# Sequencer_RevD.net
KiCad netlist of a schematic drawn in EAGLE
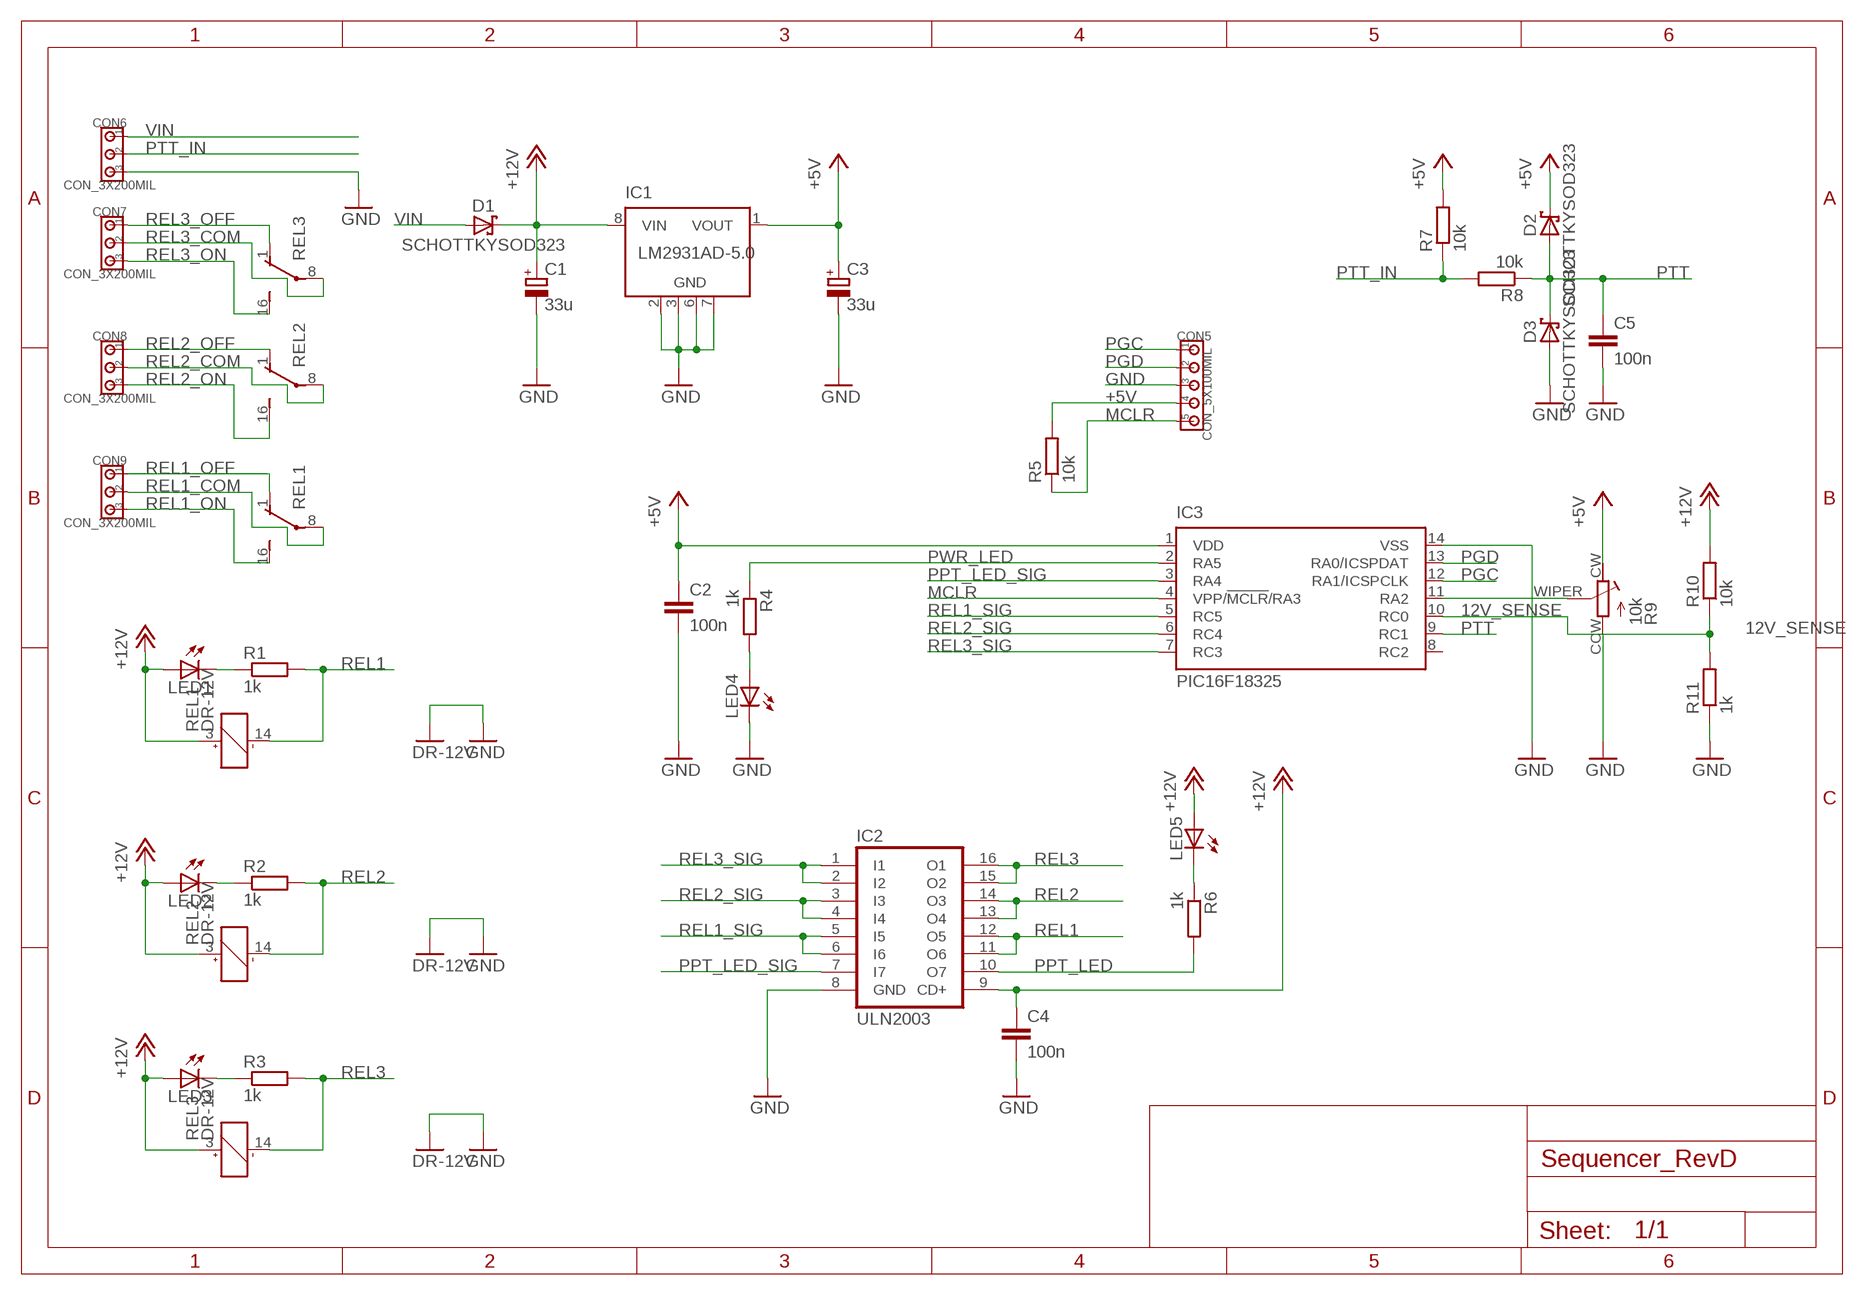
[diagram p0: schematic, sheet 1]

(export (version "E")
  (design (tool "Eeschema 10.0.6"))
  (components
    (comp (ref "C1")
      (value "33u")
      (footprint "eagle-import:SMC_C")
      (libsource (lib "eagle-import") (part "C_POLARIZEDSMC_C"))
    )
    (comp (ref "C2")
      (value "100n")
      (footprint "eagle-import:C0805")
      (libsource (lib "eagle-import") (part "CC0805"))
    )
    (comp (ref "C3")
      (value "33u")
      (footprint "eagle-import:SMC_C")
      (libsource (lib "eagle-import") (part "C_POLARIZEDSMC_C"))
    )
    (comp (ref "C4")
      (value "100n")
      (footprint "eagle-import:C0805")
      (libsource (lib "eagle-import") (part "CC0805"))
    )
    (comp (ref "C5")
      (value "100n")
      (footprint "eagle-import:C0805")
      (libsource (lib "eagle-import") (part "CC0805"))
    )
    (comp (ref "CON5")
      (value "CON_5X100MIL")
      (footprint "eagle-import:100MIL_5X")
      (libsource (lib "eagle-import") (part "CON_5X100MIL"))
    )
    (comp (ref "CON6")
      (value "CON_3X200MIL")
      (footprint "eagle-import:200MIL_3X")
      (libsource (lib "eagle-import") (part "CON_3X200MIL"))
    )
    (comp (ref "CON7")
      (value "CON_3X200MIL")
      (footprint "eagle-import:200MIL_3X")
      (libsource (lib "eagle-import") (part "CON_3X200MIL"))
    )
    (comp (ref "CON8")
      (value "CON_3X200MIL")
      (footprint "eagle-import:200MIL_3X")
      (libsource (lib "eagle-import") (part "CON_3X200MIL"))
    )
    (comp (ref "CON9")
      (value "CON_3X200MIL")
      (footprint "eagle-import:200MIL_3X")
      (libsource (lib "eagle-import") (part "CON_3X200MIL"))
    )
    (comp (ref "D1")
      (value "SCHOTTKYSOD323")
      (footprint "eagle-import:SOD323")
      (libsource (lib "eagle-import") (part "SCHOTTKYSOD323"))
    )
    (comp (ref "D2")
      (value "SCHOTTKYSOD323")
      (footprint "eagle-import:SOD323")
      (libsource (lib "eagle-import") (part "SCHOTTKYSOD323"))
    )
    (comp (ref "D3")
      (value "SCHOTTKYSOD323")
      (footprint "eagle-import:SOD323")
      (libsource (lib "eagle-import") (part "SCHOTTKYSOD323"))
    )
    (comp (ref "IC1")
      (value "LM2931AD-5.0")
      (footprint "eagle-import:SOIC8")
      (libsource (lib "eagle-import") (part "LM2931AD-5.0"))
    )
    (comp (ref "IC2")
      (value "ULN2003")
      (footprint "eagle-import:SO16")
      (libsource (lib "eagle-import") (part "ULN2003"))
    )
    (comp (ref "IC3")
      (value "PIC16F18325")
      (footprint "eagle-import:SO14")
      (libsource (lib "eagle-import") (part "PIC16F18325"))
    )
    (comp (ref "LED1")
      (value "LED0805")
      (footprint "eagle-import:LED0805")
      (libsource (lib "eagle-import") (part "LED0805"))
    )
    (comp (ref "LED2")
      (value "LED0805")
      (footprint "eagle-import:LED0805")
      (libsource (lib "eagle-import") (part "LED0805"))
    )
    (comp (ref "LED3")
      (value "LED0805")
      (footprint "eagle-import:LED0805")
      (libsource (lib "eagle-import") (part "LED0805"))
    )
    (comp (ref "LED4")
      (value "LED0805")
      (footprint "eagle-import:LED0805")
      (libsource (lib "eagle-import") (part "LED0805"))
    )
    (comp (ref "LED5")
      (value "LED0805")
      (footprint "eagle-import:LED0805")
      (libsource (lib "eagle-import") (part "LED0805"))
    )
    (comp (ref "R1")
      (value "1k")
      (footprint "eagle-import:R0805")
      (libsource (lib "eagle-import") (part "RESISTORR0805"))
    )
    (comp (ref "R2")
      (value "1k")
      (footprint "eagle-import:R0805")
      (libsource (lib "eagle-import") (part "RESISTORR0805"))
    )
    (comp (ref "R3")
      (value "1k")
      (footprint "eagle-import:R0805")
      (libsource (lib "eagle-import") (part "RESISTORR0805"))
    )
    (comp (ref "R4")
      (value "1k")
      (footprint "eagle-import:R0805")
      (libsource (lib "eagle-import") (part "RESISTORR0805"))
    )
    (comp (ref "R5")
      (value "10k")
      (footprint "eagle-import:R0805")
      (libsource (lib "eagle-import") (part "RESISTORR0805"))
    )
    (comp (ref "R6")
      (value "1k")
      (footprint "eagle-import:R0805")
      (libsource (lib "eagle-import") (part "RESISTORR0805"))
    )
    (comp (ref "R7")
      (value "10k")
      (footprint "eagle-import:R0805")
      (libsource (lib "eagle-import") (part "RESISTORR0805"))
    )
    (comp (ref "R8")
      (value "10k")
      (footprint "eagle-import:R0805")
      (libsource (lib "eagle-import") (part "RESISTORR0805"))
    )
    (comp (ref "R9")
      (value "10k")
      (footprint "eagle-import:RTRIM3314G")
      (libsource (lib "eagle-import") (part "TRIMMER3314G"))
    )
    (comp (ref "R10")
      (value "10k")
      (footprint "eagle-import:R0805")
      (libsource (lib "eagle-import") (part "RESISTORR0805"))
    )
    (comp (ref "R11")
      (value "1k")
      (footprint "eagle-import:R0805")
      (libsource (lib "eagle-import") (part "RESISTORR0805"))
    )
    (comp (ref "REL1")
      (value "DR-12V")
      (footprint "eagle-import:DR-12V")
      (libsource (lib "eagle-import") (part "DR-12V"))
    )
    (comp (ref "REL2")
      (value "DR-12V")
      (footprint "eagle-import:DR-12V")
      (libsource (lib "eagle-import") (part "DR-12V"))
    )
    (comp (ref "REL3")
      (value "DR-12V")
      (footprint "eagle-import:DR-12V")
      (libsource (lib "eagle-import") (part "DR-12V"))
    )
  )
  (nets
    (net (code "1") (name "+5V") (class "Default")
      (node (ref "C2") (pin "1") (pinfunction "1_1") (pintype "passive"))
      (node (ref "C3") (pin "+") (pinfunction "+_+") (pintype "passive"))
      (node (ref "CON5") (pin "4") (pinfunction "4_4") (pintype "passive"))
      (node (ref "D2") (pin "C") (pinfunction "C_C") (pintype "passive"))
      (node (ref "IC1") (pin "1") (pinfunction "VOUT_1") (pintype "output"))
      (node (ref "IC3") (pin "1") (pinfunction "VDD_1") (pintype "power_in"))
      (node (ref "R5") (pin "2") (pinfunction "2_2") (pintype "passive"))
      (node (ref "R7") (pin "2") (pinfunction "2_2") (pintype "passive"))
      (node (ref "R9") (pin "CW") (pinfunction "CW_CW") (pintype "passive"))
    )
    (net (code "2") (name "+12V") (class "Default")
      (node (ref "C1") (pin "+") (pinfunction "+_+") (pintype "passive"))
      (node (ref "C4") (pin "1") (pinfunction "1_1") (pintype "passive"))
      (node (ref "D1") (pin "C") (pinfunction "C_C") (pintype "passive"))
      (node (ref "IC1") (pin "8") (pinfunction "VIN_8") (pintype "passive"))
      (node (ref "IC2") (pin "9") (pinfunction "CD+_9") (pintype "passive"))
      (node (ref "LED1") (pin "A") (pinfunction "A_A") (pintype "passive"))
      (node (ref "LED2") (pin "A") (pinfunction "A_A") (pintype "passive"))
      (node (ref "LED3") (pin "A") (pinfunction "A_A") (pintype "passive"))
      (node (ref "LED5") (pin "A") (pinfunction "A_A") (pintype "passive"))
      (node (ref "R10") (pin "2") (pinfunction "2_2") (pintype "passive"))
      (node (ref "REL1") (pin "3") (pinfunction "+_3") (pintype "passive"))
      (node (ref "REL2") (pin "3") (pinfunction "+_3") (pintype "passive"))
      (node (ref "REL3") (pin "3") (pinfunction "+_3") (pintype "passive"))
    )
    (net (code "3") (name "/12V_SENSE") (class "Default")
      (node (ref "IC3") (pin "10") (pinfunction "RC0_10") (pintype "bidirectional"))
      (node (ref "R10") (pin "1") (pinfunction "1_1") (pintype "passive"))
      (node (ref "R11") (pin "2") (pinfunction "2_2") (pintype "passive"))
    )
    (net (code "4") (name "/MCLR") (class "Default")
      (node (ref "CON5") (pin "5") (pinfunction "5_5") (pintype "passive"))
      (node (ref "IC3") (pin "4") (pinfunction "VPP/~{MCLR}/RA3_4") (pintype "bidirectional"))
      (node (ref "R5") (pin "1") (pinfunction "1_1") (pintype "passive"))
    )
    (net (code "5") (name "/PGC") (class "Default")
      (node (ref "CON5") (pin "1") (pinfunction "1_1") (pintype "passive"))
      (node (ref "IC3") (pin "12") (pinfunction "RA1/ICSPCLK_12") (pintype "bidirectional"))
    )
    (net (code "6") (name "/PGD") (class "Default")
      (node (ref "CON5") (pin "2") (pinfunction "2_2") (pintype "passive"))
      (node (ref "IC3") (pin "13") (pinfunction "RA0/ICSPDAT_13") (pintype "bidirectional"))
    )
    (net (code "7") (name "/PPT_LED") (class "Default")
      (node (ref "IC2") (pin "10") (pinfunction "O7_10") (pintype "open_collector"))
      (node (ref "R6") (pin "2") (pinfunction "2_2") (pintype "passive"))
    )
    (net (code "8") (name "/PPT_LED_SIG") (class "Default")
      (node (ref "IC2") (pin "7") (pinfunction "I7_7") (pintype "input"))
      (node (ref "IC3") (pin "3") (pinfunction "RA4_3") (pintype "bidirectional"))
    )
    (net (code "9") (name "/PTT") (class "Default")
      (node (ref "C5") (pin "1") (pinfunction "1_1") (pintype "passive"))
      (node (ref "D2") (pin "A") (pinfunction "A_A") (pintype "passive"))
      (node (ref "D3") (pin "C") (pinfunction "C_C") (pintype "passive"))
      (node (ref "IC3") (pin "9") (pinfunction "RC1_9") (pintype "bidirectional"))
      (node (ref "R8") (pin "1") (pinfunction "1_1") (pintype "passive"))
    )
    (net (code "10") (name "/PTT_IN") (class "Default")
      (node (ref "CON6") (pin "2") (pinfunction "2_2") (pintype "passive"))
      (node (ref "R7") (pin "1") (pinfunction "1_1") (pintype "passive"))
      (node (ref "R8") (pin "2") (pinfunction "2_2") (pintype "passive"))
    )
    (net (code "11") (name "/PWR_LED") (class "Default")
      (node (ref "IC3") (pin "2") (pinfunction "RA5_2") (pintype "input"))
      (node (ref "R4") (pin "1") (pinfunction "1_1") (pintype "passive"))
    )
    (net (code "12") (name "/REL1") (class "Default")
      (node (ref "IC2") (pin "11") (pinfunction "O6_11") (pintype "open_collector"))
      (node (ref "IC2") (pin "12") (pinfunction "O5_12") (pintype "open_collector"))
      (node (ref "R1") (pin "2") (pinfunction "2_2") (pintype "passive"))
      (node (ref "REL1") (pin "14") (pinfunction "-_14") (pintype "passive"))
    )
    (net (code "13") (name "/REL1_COM") (class "Default")
      (node (ref "CON9") (pin "2") (pinfunction "2_2") (pintype "passive"))
      (node (ref "REL1") (pin "8") (pinfunction "P_8") (pintype "passive"))
    )
    (net (code "14") (name "/REL1_OFF") (class "Default")
      (node (ref "CON9") (pin "1") (pinfunction "1_1") (pintype "passive"))
      (node (ref "REL1") (pin "1") (pinfunction "O_1") (pintype "passive"))
    )
    (net (code "15") (name "/REL1_ON") (class "Default")
      (node (ref "CON9") (pin "3") (pinfunction "3_3") (pintype "passive"))
      (node (ref "REL1") (pin "16") (pinfunction "S_16") (pintype "passive"))
    )
    (net (code "16") (name "/REL1_SIG") (class "Default")
      (node (ref "IC2") (pin "5") (pinfunction "I5_5") (pintype "input"))
      (node (ref "IC2") (pin "6") (pinfunction "I6_6") (pintype "input"))
      (node (ref "IC3") (pin "5") (pinfunction "RC5_5") (pintype "bidirectional"))
    )
    (net (code "17") (name "/REL2") (class "Default")
      (node (ref "IC2") (pin "13") (pinfunction "O4_13") (pintype "open_collector"))
      (node (ref "IC2") (pin "14") (pinfunction "O3_14") (pintype "open_collector"))
      (node (ref "R2") (pin "2") (pinfunction "2_2") (pintype "passive"))
      (node (ref "REL2") (pin "14") (pinfunction "-_14") (pintype "passive"))
    )
    (net (code "18") (name "/REL2_COM") (class "Default")
      (node (ref "CON8") (pin "2") (pinfunction "2_2") (pintype "passive"))
      (node (ref "REL2") (pin "8") (pinfunction "P_8") (pintype "passive"))
    )
    (net (code "19") (name "/REL2_OFF") (class "Default")
      (node (ref "CON8") (pin "1") (pinfunction "1_1") (pintype "passive"))
      (node (ref "REL2") (pin "1") (pinfunction "O_1") (pintype "passive"))
    )
    (net (code "20") (name "/REL2_ON") (class "Default")
      (node (ref "CON8") (pin "3") (pinfunction "3_3") (pintype "passive"))
      (node (ref "REL2") (pin "16") (pinfunction "S_16") (pintype "passive"))
    )
    (net (code "21") (name "/REL2_SIG") (class "Default")
      (node (ref "IC2") (pin "3") (pinfunction "I3_3") (pintype "input"))
      (node (ref "IC2") (pin "4") (pinfunction "I4_4") (pintype "input"))
      (node (ref "IC3") (pin "6") (pinfunction "RC4_6") (pintype "bidirectional"))
    )
    (net (code "22") (name "/REL3") (class "Default")
      (node (ref "IC2") (pin "15") (pinfunction "O2_15") (pintype "open_collector"))
      (node (ref "IC2") (pin "16") (pinfunction "O1_16") (pintype "open_collector"))
      (node (ref "R3") (pin "2") (pinfunction "2_2") (pintype "passive"))
      (node (ref "REL3") (pin "14") (pinfunction "-_14") (pintype "passive"))
    )
    (net (code "23") (name "/REL3_COM") (class "Default")
      (node (ref "CON7") (pin "2") (pinfunction "2_2") (pintype "passive"))
      (node (ref "REL3") (pin "8") (pinfunction "P_8") (pintype "passive"))
    )
    (net (code "24") (name "/REL3_OFF") (class "Default")
      (node (ref "CON7") (pin "1") (pinfunction "1_1") (pintype "passive"))
      (node (ref "REL3") (pin "1") (pinfunction "O_1") (pintype "passive"))
    )
    (net (code "25") (name "/REL3_ON") (class "Default")
      (node (ref "CON7") (pin "3") (pinfunction "3_3") (pintype "passive"))
      (node (ref "REL3") (pin "16") (pinfunction "S_16") (pintype "passive"))
    )
    (net (code "26") (name "/REL3_SIG") (class "Default")
      (node (ref "IC2") (pin "1") (pinfunction "I1_1") (pintype "input"))
      (node (ref "IC2") (pin "2") (pinfunction "I2_2") (pintype "input"))
      (node (ref "IC3") (pin "7") (pinfunction "RC3_7") (pintype "bidirectional"))
    )
    (net (code "27") (name "/VIN") (class "Default")
      (node (ref "CON6") (pin "1") (pinfunction "1_1") (pintype "passive"))
      (node (ref "D1") (pin "A") (pinfunction "A_A") (pintype "passive"))
    )
    (net (code "28") (name "GND") (class "Default")
      (node (ref "C1") (pin "-") (pinfunction "-_-") (pintype "passive"))
      (node (ref "C2") (pin "2") (pinfunction "2_2") (pintype "passive"))
      (node (ref "C3") (pin "-") (pinfunction "-_-") (pintype "passive"))
      (node (ref "C4") (pin "2") (pinfunction "2_2") (pintype "passive"))
      (node (ref "C5") (pin "2") (pinfunction "2_2") (pintype "passive"))
      (node (ref "CON5") (pin "3") (pinfunction "3_3") (pintype "passive"))
      (node (ref "CON6") (pin "3") (pinfunction "3_3") (pintype "passive"))
      (node (ref "D3") (pin "A") (pinfunction "A_A") (pintype "passive"))
      (node (ref "IC1") (pin "2") (pinfunction "GND_2") (pintype "power_in"))
      (node (ref "IC1") (pin "3") (pinfunction "GND_3") (pintype "power_in"))
      (node (ref "IC1") (pin "6") (pinfunction "GND_6") (pintype "power_in"))
      (node (ref "IC1") (pin "7") (pinfunction "GND_7") (pintype "power_in"))
      (node (ref "IC2") (pin "8") (pinfunction "GND_8") (pintype "power_in"))
      (node (ref "IC3") (pin "14") (pinfunction "VSS_14") (pintype "power_in"))
      (node (ref "LED4") (pin "C") (pinfunction "C_C") (pintype "passive"))
      (node (ref "R11") (pin "1") (pinfunction "1_1") (pintype "passive"))
      (node (ref "R9") (pin "CCW") (pinfunction "CCW_CCW") (pintype "passive"))
      (node (ref "REL1") (pin "9") (pinfunction "GND_9") (pintype "power_in"))
      (node (ref "REL2") (pin "9") (pinfunction "GND_9") (pintype "power_in"))
      (node (ref "REL3") (pin "9") (pinfunction "GND_9") (pintype "power_in"))
    )
    (net (code "29") (name "Net-(IC3-RA2)") (class "Default")
      (node (ref "IC3") (pin "11") (pinfunction "RA2_11") (pintype "bidirectional"))
      (node (ref "R9") (pin "WIPER") (pinfunction "WIPER_WIPER") (pintype "passive"))
    )
    (net (code "30") (name "Net-(LED1-PadC)") (class "Default")
      (node (ref "LED1") (pin "C") (pinfunction "C_C") (pintype "passive"))
      (node (ref "R1") (pin "1") (pinfunction "1_1") (pintype "passive"))
    )
    (net (code "31") (name "Net-(LED2-PadC)") (class "Default")
      (node (ref "LED2") (pin "C") (pinfunction "C_C") (pintype "passive"))
      (node (ref "R2") (pin "1") (pinfunction "1_1") (pintype "passive"))
    )
    (net (code "32") (name "Net-(LED3-PadC)") (class "Default")
      (node (ref "LED3") (pin "C") (pinfunction "C_C") (pintype "passive"))
      (node (ref "R3") (pin "1") (pinfunction "1_1") (pintype "passive"))
    )
    (net (code "33") (name "Net-(LED4-PadA)") (class "Default")
      (node (ref "LED4") (pin "A") (pinfunction "A_A") (pintype "passive"))
      (node (ref "R4") (pin "2") (pinfunction "2_2") (pintype "passive"))
    )
    (net (code "34") (name "Net-(LED5-PadC)") (class "Default")
      (node (ref "LED5") (pin "C") (pinfunction "C_C") (pintype "passive"))
      (node (ref "R6") (pin "1") (pinfunction "1_1") (pintype "passive"))
    )
    (net (code "35") (name "unconnected-(IC3-RC2-Pad8)") (class "Default")
      (node (ref "IC3") (pin "8") (pinfunction "RC2_8") (pintype "bidirectional"))
    )
  )
)
